# DCC_cDecoder.net
KiCad netlist of a schematic drawn in EAGLE
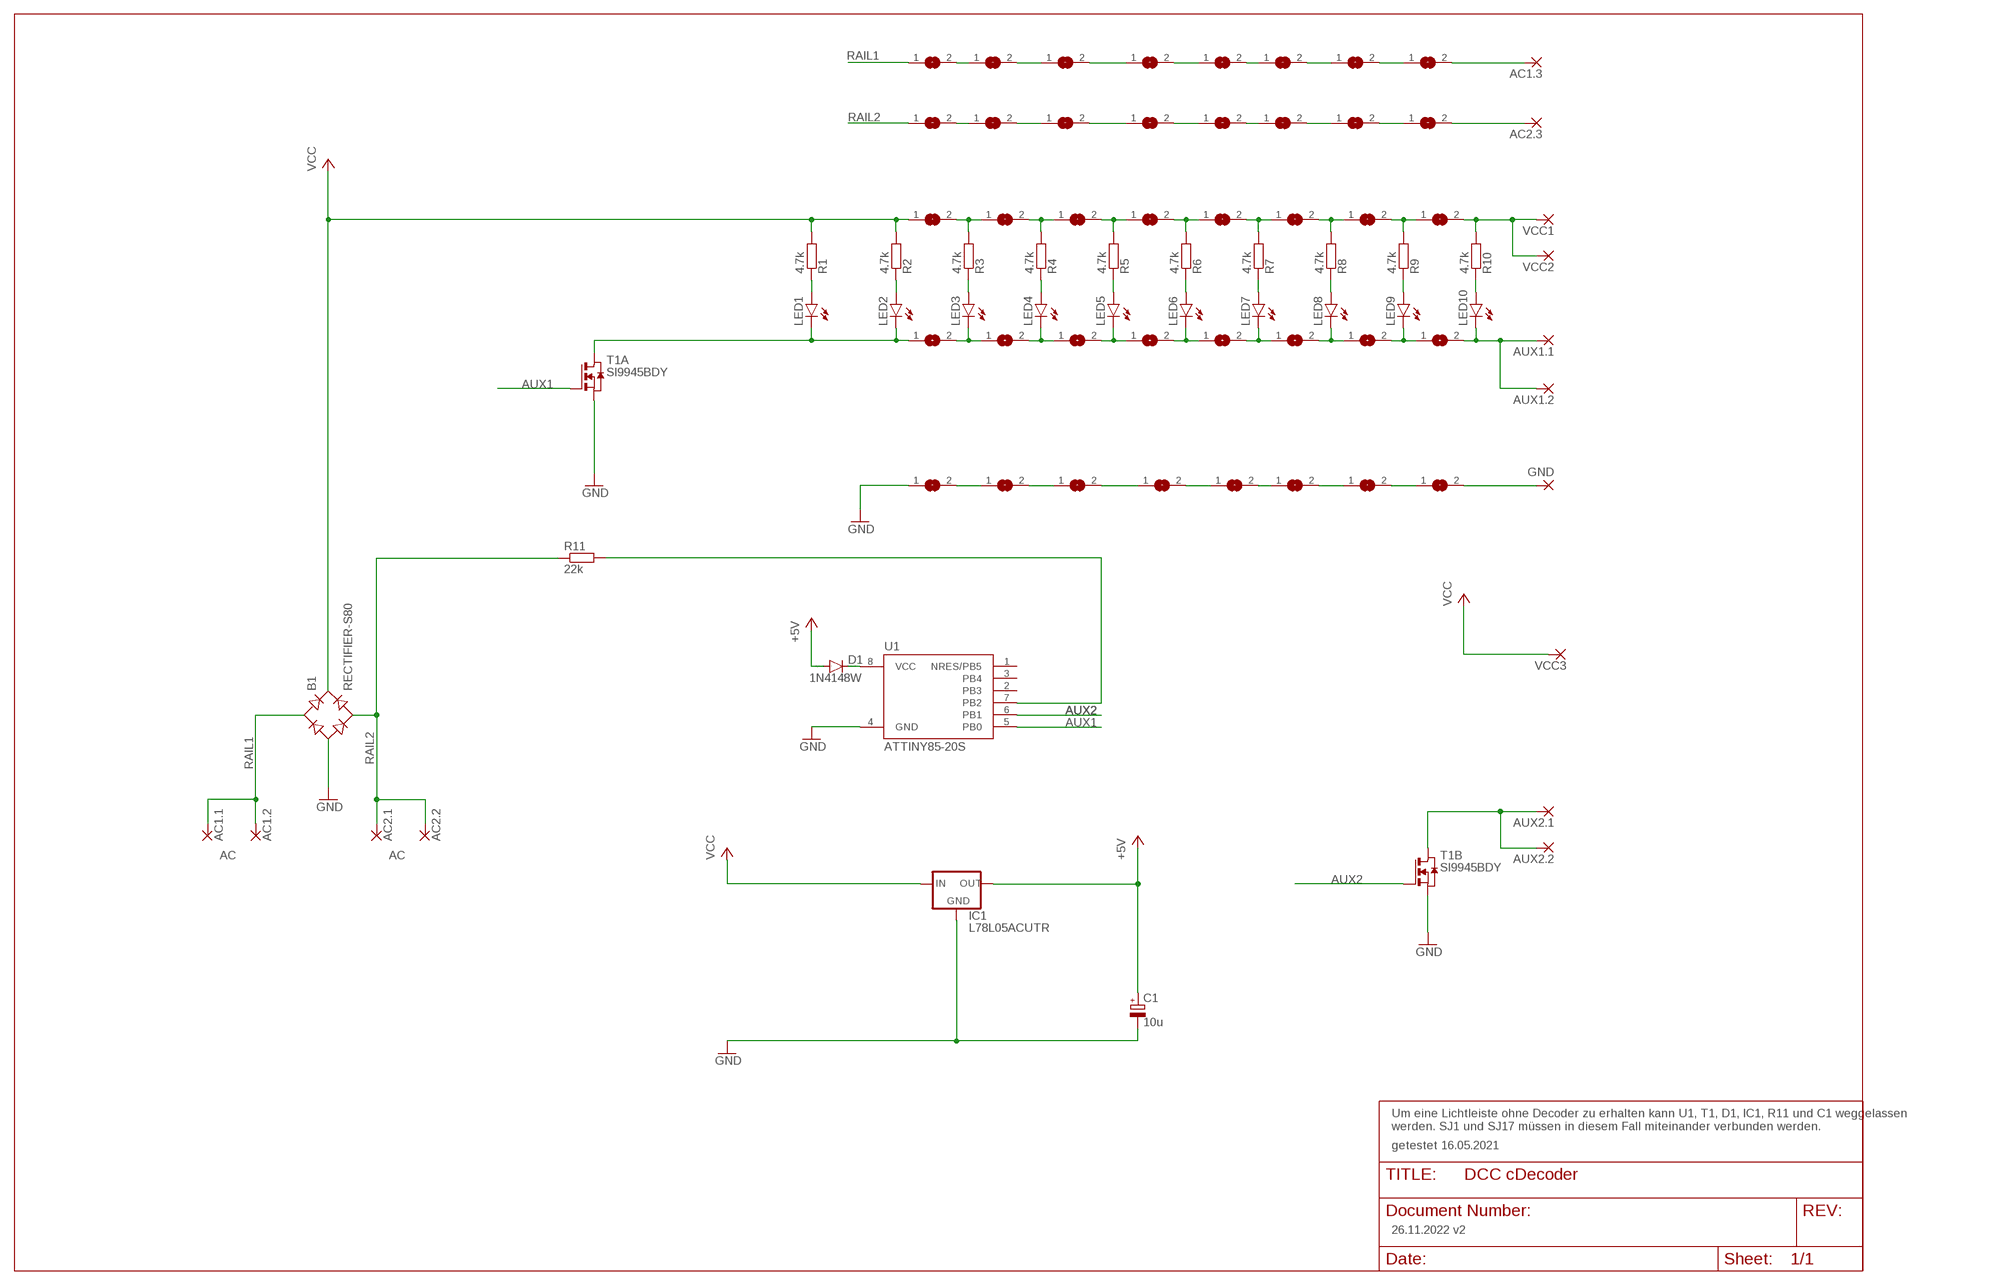
[diagram p0: schematic, sheet 1]

(export (version "E")
  (design (tool "Eeschema 10.0.6"))
  (components
    (comp (ref "AC1.1")
      (value "AC1.1")
      (footprint "eagle-import:SMD1,27-2,54")
      (libsource (lib "eagle-import") (part "SMD2"))
    )
    (comp (ref "AC1.2")
      (value "AC1.2")
      (footprint "eagle-import:SMD1,27-2,54")
      (libsource (lib "eagle-import") (part "SMD2"))
    )
    (comp (ref "AC1.3")
      (value "AC1.3")
      (footprint "eagle-import:SMD1,27-2,54")
      (libsource (lib "eagle-import") (part "SMD2"))
    )
    (comp (ref "AC2.1")
      (value "AC2.1")
      (footprint "eagle-import:SMD1,27-2,54")
      (libsource (lib "eagle-import") (part "SMD2"))
    )
    (comp (ref "AC2.2")
      (value "AC2.2")
      (footprint "eagle-import:SMD1,27-2,54")
      (libsource (lib "eagle-import") (part "SMD2"))
    )
    (comp (ref "AC2.3")
      (value "AC2.3")
      (footprint "eagle-import:SMD1,27-2,54")
      (libsource (lib "eagle-import") (part "SMD2"))
    )
    (comp (ref "AUX1.1")
      (value "AUX1.1")
      (footprint "eagle-import:SMD1,27-2,54")
      (libsource (lib "eagle-import") (part "SMD2"))
    )
    (comp (ref "AUX1.2")
      (value "AUX1.2")
      (footprint "eagle-import:SMD1,27-2,54")
      (libsource (lib "eagle-import") (part "SMD2"))
    )
    (comp (ref "AUX2.1")
      (value "AUX2.1")
      (footprint "eagle-import:SMD1,27-2,54")
      (libsource (lib "eagle-import") (part "SMD2"))
    )
    (comp (ref "AUX2.2")
      (value "AUX2.2")
      (footprint "eagle-import:SMD1,27-2,54")
      (libsource (lib "eagle-import") (part "SMD2"))
    )
    (comp (ref "B1")
      (value "RECTIFIER-S80")
      (footprint "eagle-import:TO-269AA")
      (libsource (lib "eagle-import") (part "RECTIFIER-S80"))
    )
    (comp (ref "C1")
      (value "10u")
      (footprint "eagle-import:A_3216-18W")
      (libsource (lib "eagle-import") (part "CPOL-EUA/3216-18W"))
    )
    (comp (ref "D1")
      (value "1N4148W")
      (footprint "eagle-import:SOD-123_MINI-SMA")
      (libsource (lib "eagle-import") (part "CGRM400-G1"))
    )
    (comp (ref "GND")
      (value "SMD2")
      (footprint "eagle-import:SMD1,27-2,54")
      (libsource (lib "eagle-import") (part "SMD2"))
    )
    (comp (ref "IC1")
      (value "L78L05ACUTR")
      (footprint "eagle-import:SOT89R")
      (libsource (lib "eagle-import") (part "L78L05ACUTR"))
    )
    (comp (ref "LED1")
      (value "LEDCHIPLED_0805")
      (footprint "eagle-import:CHIPLED_0805")
      (libsource (lib "eagle-import") (part "LEDCHIPLED_0805"))
    )
    (comp (ref "LED2")
      (value "LEDCHIPLED_0805")
      (footprint "eagle-import:CHIPLED_0805")
      (libsource (lib "eagle-import") (part "LEDCHIPLED_0805"))
    )
    (comp (ref "LED3")
      (value "LEDCHIPLED_0805")
      (footprint "eagle-import:CHIPLED_0805")
      (libsource (lib "eagle-import") (part "LEDCHIPLED_0805"))
    )
    (comp (ref "LED4")
      (value "LEDCHIPLED_0805")
      (footprint "eagle-import:CHIPLED_0805")
      (libsource (lib "eagle-import") (part "LEDCHIPLED_0805"))
    )
    (comp (ref "LED5")
      (value "LEDCHIPLED_0805")
      (footprint "eagle-import:CHIPLED_0805")
      (libsource (lib "eagle-import") (part "LEDCHIPLED_0805"))
    )
    (comp (ref "LED6")
      (value "LEDCHIPLED_0805")
      (footprint "eagle-import:CHIPLED_0805")
      (libsource (lib "eagle-import") (part "LEDCHIPLED_0805"))
    )
    (comp (ref "LED7")
      (value "LEDCHIPLED_0805")
      (footprint "eagle-import:CHIPLED_0805")
      (libsource (lib "eagle-import") (part "LEDCHIPLED_0805"))
    )
    (comp (ref "LED8")
      (value "LEDCHIPLED_0805")
      (footprint "eagle-import:CHIPLED_0805")
      (libsource (lib "eagle-import") (part "LEDCHIPLED_0805"))
    )
    (comp (ref "LED9")
      (value "LEDCHIPLED_0805")
      (footprint "eagle-import:CHIPLED_0805")
      (libsource (lib "eagle-import") (part "LEDCHIPLED_0805"))
    )
    (comp (ref "LED10")
      (value "LEDCHIPLED_0805")
      (footprint "eagle-import:CHIPLED_0805")
      (libsource (lib "eagle-import") (part "LEDCHIPLED_0805"))
    )
    (comp (ref "R1")
      (value "4.7k")
      (footprint "eagle-import:R0805")
      (libsource (lib "eagle-import") (part "R-EU_R0805"))
    )
    (comp (ref "R2")
      (value "4.7k")
      (footprint "eagle-import:R0805")
      (libsource (lib "eagle-import") (part "R-EU_R0805"))
    )
    (comp (ref "R3")
      (value "4.7k")
      (footprint "eagle-import:R0805")
      (libsource (lib "eagle-import") (part "R-EU_R0805"))
    )
    (comp (ref "R4")
      (value "4.7k")
      (footprint "eagle-import:R0805")
      (libsource (lib "eagle-import") (part "R-EU_R0805"))
    )
    (comp (ref "R5")
      (value "4.7k")
      (footprint "eagle-import:R0805")
      (libsource (lib "eagle-import") (part "R-EU_R0805"))
    )
    (comp (ref "R6")
      (value "4.7k")
      (footprint "eagle-import:R0805")
      (libsource (lib "eagle-import") (part "R-EU_R0805"))
    )
    (comp (ref "R7")
      (value "4.7k")
      (footprint "eagle-import:R0805")
      (libsource (lib "eagle-import") (part "R-EU_R0805"))
    )
    (comp (ref "R8")
      (value "4.7k")
      (footprint "eagle-import:R0805")
      (libsource (lib "eagle-import") (part "R-EU_R0805"))
    )
    (comp (ref "R9")
      (value "4.7k")
      (footprint "eagle-import:R0805")
      (libsource (lib "eagle-import") (part "R-EU_R0805"))
    )
    (comp (ref "R10")
      (value "4.7k")
      (footprint "eagle-import:R0805")
      (libsource (lib "eagle-import") (part "R-EU_R0805"))
    )
    (comp (ref "R11")
      (value "22k")
      (footprint "eagle-import:R0805")
      (libsource (lib "eagle-import") (part "R-EU_R0805"))
    )
    (comp (ref "SJ1")
      (value "SJC")
      (footprint "eagle-import:SJC")
      (libsource (lib "eagle-import") (part "SJC"))
    )
    (comp (ref "SJ2")
      (value "SJC")
      (footprint "eagle-import:SJC")
      (libsource (lib "eagle-import") (part "SJC"))
    )
    (comp (ref "SJ3")
      (value "SJC")
      (footprint "eagle-import:SJC")
      (libsource (lib "eagle-import") (part "SJC"))
    )
    (comp (ref "SJ4")
      (value "SJC")
      (footprint "eagle-import:SJC")
      (libsource (lib "eagle-import") (part "SJC"))
    )
    (comp (ref "SJ5")
      (value "SJC")
      (footprint "eagle-import:SJC")
      (libsource (lib "eagle-import") (part "SJC"))
    )
    (comp (ref "SJ6")
      (value "SJC")
      (footprint "eagle-import:SJC")
      (libsource (lib "eagle-import") (part "SJC"))
    )
    (comp (ref "SJ7")
      (value "SJC")
      (footprint "eagle-import:SJC")
      (libsource (lib "eagle-import") (part "SJC"))
    )
    (comp (ref "SJ8")
      (value "SJC")
      (footprint "eagle-import:SJC")
      (libsource (lib "eagle-import") (part "SJC"))
    )
    (comp (ref "SJ9")
      (value "SJC")
      (footprint "eagle-import:SJC")
      (libsource (lib "eagle-import") (part "SJC"))
    )
    (comp (ref "SJ10")
      (value "SJC")
      (footprint "eagle-import:SJC")
      (libsource (lib "eagle-import") (part "SJC"))
    )
    (comp (ref "SJ11")
      (value "SJC")
      (footprint "eagle-import:SJC")
      (libsource (lib "eagle-import") (part "SJC"))
    )
    (comp (ref "SJ12")
      (value "SJC")
      (footprint "eagle-import:SJC")
      (libsource (lib "eagle-import") (part "SJC"))
    )
    (comp (ref "SJ13")
      (value "SJC")
      (footprint "eagle-import:SJC")
      (libsource (lib "eagle-import") (part "SJC"))
    )
    (comp (ref "SJ14")
      (value "SJC")
      (footprint "eagle-import:SJC")
      (libsource (lib "eagle-import") (part "SJC"))
    )
    (comp (ref "SJ15")
      (value "SJC")
      (footprint "eagle-import:SJC")
      (libsource (lib "eagle-import") (part "SJC"))
    )
    (comp (ref "SJ16")
      (value "SJC")
      (footprint "eagle-import:SJC")
      (libsource (lib "eagle-import") (part "SJC"))
    )
    (comp (ref "SJ17")
      (value "SJ")
      (footprint "eagle-import:SJ")
      (libsource (lib "eagle-import") (part "SJ"))
    )
    (comp (ref "SJ18")
      (value "SJ")
      (footprint "eagle-import:SJ")
      (libsource (lib "eagle-import") (part "SJ"))
    )
    (comp (ref "SJ19")
      (value "SJ")
      (footprint "eagle-import:SJ")
      (libsource (lib "eagle-import") (part "SJ"))
    )
    (comp (ref "SJ20")
      (value "SJ")
      (footprint "eagle-import:SJ")
      (libsource (lib "eagle-import") (part "SJ"))
    )
    (comp (ref "SJ21")
      (value "SJ")
      (footprint "eagle-import:SJ")
      (libsource (lib "eagle-import") (part "SJ"))
    )
    (comp (ref "SJ22")
      (value "SJ")
      (footprint "eagle-import:SJ")
      (libsource (lib "eagle-import") (part "SJ"))
    )
    (comp (ref "SJ23")
      (value "SJ")
      (footprint "eagle-import:SJ")
      (libsource (lib "eagle-import") (part "SJ"))
    )
    (comp (ref "SJ24")
      (value "SJ")
      (footprint "eagle-import:SJ")
      (libsource (lib "eagle-import") (part "SJ"))
    )
    (comp (ref "SJ25")
      (value "SJC")
      (footprint "eagle-import:SJC")
      (libsource (lib "eagle-import") (part "SJC"))
    )
    (comp (ref "SJ26")
      (value "SJC")
      (footprint "eagle-import:SJC")
      (libsource (lib "eagle-import") (part "SJC"))
    )
    (comp (ref "SJ27")
      (value "SJC")
      (footprint "eagle-import:SJC")
      (libsource (lib "eagle-import") (part "SJC"))
    )
    (comp (ref "SJ28")
      (value "SJC")
      (footprint "eagle-import:SJC")
      (libsource (lib "eagle-import") (part "SJC"))
    )
    (comp (ref "SJ29")
      (value "SJC")
      (footprint "eagle-import:SJC")
      (libsource (lib "eagle-import") (part "SJC"))
    )
    (comp (ref "SJ30")
      (value "SJC")
      (footprint "eagle-import:SJC")
      (libsource (lib "eagle-import") (part "SJC"))
    )
    (comp (ref "SJ31")
      (value "SJC")
      (footprint "eagle-import:SJC")
      (libsource (lib "eagle-import") (part "SJC"))
    )
    (comp (ref "SJ32")
      (value "SJC")
      (footprint "eagle-import:SJC")
      (libsource (lib "eagle-import") (part "SJC"))
    )
    (comp (ref "SJ33")
      (value "SJC")
      (footprint "eagle-import:SJC")
      (libsource (lib "eagle-import") (part "SJC"))
    )
    (comp (ref "SJ34")
      (value "SJC")
      (footprint "eagle-import:SJC")
      (libsource (lib "eagle-import") (part "SJC"))
    )
    (comp (ref "SJ35")
      (value "SJC")
      (footprint "eagle-import:SJC")
      (libsource (lib "eagle-import") (part "SJC"))
    )
    (comp (ref "SJ36")
      (value "SJC")
      (footprint "eagle-import:SJC")
      (libsource (lib "eagle-import") (part "SJC"))
    )
    (comp (ref "SJ37")
      (value "SJC")
      (footprint "eagle-import:SJC")
      (libsource (lib "eagle-import") (part "SJC"))
    )
    (comp (ref "SJ38")
      (value "SJC")
      (footprint "eagle-import:SJC")
      (libsource (lib "eagle-import") (part "SJC"))
    )
    (comp (ref "SJ39")
      (value "SJC")
      (footprint "eagle-import:SJC")
      (libsource (lib "eagle-import") (part "SJC"))
    )
    (comp (ref "SJ40")
      (value "SJC")
      (footprint "eagle-import:SJC")
      (libsource (lib "eagle-import") (part "SJC"))
    )
    (comp (ref "T1")
      (value "SI9945BDY")
      (footprint "eagle-import:SO8")
      (libsource (lib "eagle-import") (part "NMOS2SO8"))
    )
    (comp (ref "U1")
      (value "ATTINY85-20S")
      (footprint "eagle-import:SOIC8_EIAJ_208MIL")
      (libsource (lib "eagle-import") (part "ATTINY85S-20"))
    )
    (comp (ref "VCC1")
      (value "VCC1")
      (footprint "eagle-import:SMD1,27-2,54")
      (libsource (lib "eagle-import") (part "SMD2"))
    )
    (comp (ref "VCC2")
      (value "VCC2")
      (footprint "eagle-import:SMD1,27-2,54")
      (libsource (lib "eagle-import") (part "SMD2"))
    )
    (comp (ref "VCC3")
      (value "VCC3")
      (footprint "eagle-import:SMD1,27-2,54")
      (libsource (lib "eagle-import") (part "SMD2"))
    )
  )
  (nets
    (net (code "1") (name "+5V") (class "Default")
      (node (ref "C1") (pin "+") (pinfunction "+_+") (pintype "passive"))
      (node (ref "D1") (pin "A") (pinfunction "A_A") (pintype "passive"))
      (node (ref "IC1") (pin "2") (pinfunction "OUT_2") (pintype "passive"))
    )
    (net (code "2") (name "/AUX1") (class "Default")
      (node (ref "T1") (pin "2") (pinfunction "G_2") (pintype "passive"))
      (node (ref "U1") (pin "5") (pinfunction "PB0_5") (pintype "bidirectional"))
    )
    (net (code "3") (name "/AUX2") (class "Default")
      (node (ref "T1") (pin "4") (pinfunction "G_4") (pintype "passive"))
      (node (ref "U1") (pin "6") (pinfunction "PB1_6") (pintype "bidirectional"))
    )
    (net (code "4") (name "/RAIL1") (class "Default")
      (node (ref "AC1.1") (pin "1") (pinfunction "P_1") (pintype "passive"))
      (node (ref "AC1.2") (pin "1") (pinfunction "P_1") (pintype "passive"))
      (node (ref "B1") (pin "AC1") (pinfunction "AC1_AC1") (pintype "passive"))
      (node (ref "SJ25") (pin "1") (pinfunction "1_1") (pintype "passive"))
    )
    (net (code "5") (name "/RAIL2") (class "Default")
      (node (ref "AC2.1") (pin "1") (pinfunction "P_1") (pintype "passive"))
      (node (ref "AC2.2") (pin "1") (pinfunction "P_1") (pintype "passive"))
      (node (ref "B1") (pin "AC2") (pinfunction "AC2_AC2") (pintype "passive"))
      (node (ref "R11") (pin "1") (pinfunction "1_1") (pintype "passive"))
      (node (ref "SJ33") (pin "1") (pinfunction "1_1") (pintype "passive"))
    )
    (net (code "6") (name "GND") (class "Default")
      (node (ref "B1") (pin "-") (pinfunction "-_-") (pintype "passive"))
      (node (ref "C1") (pin "-") (pinfunction "-_-") (pintype "passive"))
      (node (ref "IC1") (pin "3") (pinfunction "GND_3") (pintype "input"))
      (node (ref "IC1") (pin "4") (pinfunction "GND_4") (pintype "input"))
      (node (ref "SJ1") (pin "1") (pinfunction "1_1") (pintype "passive"))
      (node (ref "T1") (pin "1") (pinfunction "S_1") (pintype "passive"))
      (node (ref "T1") (pin "3") (pinfunction "S_3") (pintype "passive"))
      (node (ref "U1") (pin "4") (pinfunction "GND_4") (pintype "power_in"))
    )
    (net (code "7") (name "Net-(AC1.3-P)") (class "Default")
      (node (ref "AC1.3") (pin "1") (pinfunction "P_1") (pintype "passive"))
      (node (ref "SJ32") (pin "2") (pinfunction "2_2") (pintype "passive"))
    )
    (net (code "8") (name "Net-(AC2.3-P)") (class "Default")
      (node (ref "AC2.3") (pin "1") (pinfunction "P_1") (pintype "passive"))
      (node (ref "SJ40") (pin "2") (pinfunction "2_2") (pintype "passive"))
    )
    (net (code "9") (name "Net-(AUX1.1-P)") (class "Default")
      (node (ref "AUX1.1") (pin "1") (pinfunction "P_1") (pintype "passive"))
      (node (ref "AUX1.2") (pin "1") (pinfunction "P_1") (pintype "passive"))
      (node (ref "LED10") (pin "C") (pinfunction "C_C") (pintype "passive"))
      (node (ref "SJ24") (pin "2") (pinfunction "2_2") (pintype "passive"))
    )
    (net (code "10") (name "Net-(AUX2.1-P)") (class "Default")
      (node (ref "AUX2.1") (pin "1") (pinfunction "P_1") (pintype "passive"))
      (node (ref "AUX2.2") (pin "1") (pinfunction "P_1") (pintype "passive"))
      (node (ref "T1") (pin "5") (pinfunction "D_5") (pintype "passive"))
      (node (ref "T1") (pin "6") (pinfunction "D_6") (pintype "passive"))
    )
    (net (code "11") (name "Net-(GND-P)") (class "Default")
      (node (ref "GND") (pin "1") (pinfunction "P_1") (pintype "passive"))
      (node (ref "SJ15") (pin "2") (pinfunction "2_2") (pintype "passive"))
    )
    (net (code "12") (name "Net-(LED1-PadA)") (class "Default")
      (node (ref "LED1") (pin "A") (pinfunction "A_A") (pintype "passive"))
      (node (ref "R1") (pin "1") (pinfunction "1_1") (pintype "passive"))
    )
    (net (code "13") (name "Net-(LED1-PadC)") (class "Default")
      (node (ref "LED1") (pin "C") (pinfunction "C_C") (pintype "passive"))
      (node (ref "LED2") (pin "C") (pinfunction "C_C") (pintype "passive"))
      (node (ref "SJ17") (pin "1") (pinfunction "1_1") (pintype "passive"))
      (node (ref "T1") (pin "7") (pinfunction "D_7") (pintype "passive"))
      (node (ref "T1") (pin "8") (pinfunction "D_8") (pintype "passive"))
    )
    (net (code "14") (name "Net-(LED2-PadA)") (class "Default")
      (node (ref "LED2") (pin "A") (pinfunction "A_A") (pintype "passive"))
      (node (ref "R2") (pin "1") (pinfunction "1_1") (pintype "passive"))
    )
    (net (code "15") (name "Net-(LED3-PadA)") (class "Default")
      (node (ref "LED3") (pin "A") (pinfunction "A_A") (pintype "passive"))
      (node (ref "R3") (pin "1") (pinfunction "1_1") (pintype "passive"))
    )
    (net (code "16") (name "Net-(LED3-PadC)") (class "Default")
      (node (ref "LED3") (pin "C") (pinfunction "C_C") (pintype "passive"))
      (node (ref "SJ17") (pin "2") (pinfunction "2_2") (pintype "passive"))
      (node (ref "SJ18") (pin "1") (pinfunction "1_1") (pintype "passive"))
    )
    (net (code "17") (name "Net-(LED4-PadA)") (class "Default")
      (node (ref "LED4") (pin "A") (pinfunction "A_A") (pintype "passive"))
      (node (ref "R4") (pin "1") (pinfunction "1_1") (pintype "passive"))
    )
    (net (code "18") (name "Net-(LED4-PadC)") (class "Default")
      (node (ref "LED4") (pin "C") (pinfunction "C_C") (pintype "passive"))
      (node (ref "SJ18") (pin "2") (pinfunction "2_2") (pintype "passive"))
      (node (ref "SJ19") (pin "1") (pinfunction "1_1") (pintype "passive"))
    )
    (net (code "19") (name "Net-(LED5-PadA)") (class "Default")
      (node (ref "LED5") (pin "A") (pinfunction "A_A") (pintype "passive"))
      (node (ref "R5") (pin "1") (pinfunction "1_1") (pintype "passive"))
    )
    (net (code "20") (name "Net-(LED5-PadC)") (class "Default")
      (node (ref "LED5") (pin "C") (pinfunction "C_C") (pintype "passive"))
      (node (ref "SJ19") (pin "2") (pinfunction "2_2") (pintype "passive"))
      (node (ref "SJ20") (pin "1") (pinfunction "1_1") (pintype "passive"))
    )
    (net (code "21") (name "Net-(LED6-PadA)") (class "Default")
      (node (ref "LED6") (pin "A") (pinfunction "A_A") (pintype "passive"))
      (node (ref "R6") (pin "1") (pinfunction "1_1") (pintype "passive"))
    )
    (net (code "22") (name "Net-(LED6-PadC)") (class "Default")
      (node (ref "LED6") (pin "C") (pinfunction "C_C") (pintype "passive"))
      (node (ref "SJ20") (pin "2") (pinfunction "2_2") (pintype "passive"))
      (node (ref "SJ21") (pin "1") (pinfunction "1_1") (pintype "passive"))
    )
    (net (code "23") (name "Net-(LED7-PadA)") (class "Default")
      (node (ref "LED7") (pin "A") (pinfunction "A_A") (pintype "passive"))
      (node (ref "R7") (pin "1") (pinfunction "1_1") (pintype "passive"))
    )
    (net (code "24") (name "Net-(LED7-PadC)") (class "Default")
      (node (ref "LED7") (pin "C") (pinfunction "C_C") (pintype "passive"))
      (node (ref "SJ21") (pin "2") (pinfunction "2_2") (pintype "passive"))
      (node (ref "SJ22") (pin "1") (pinfunction "1_1") (pintype "passive"))
    )
    (net (code "25") (name "Net-(LED8-PadA)") (class "Default")
      (node (ref "LED8") (pin "A") (pinfunction "A_A") (pintype "passive"))
      (node (ref "R8") (pin "1") (pinfunction "1_1") (pintype "passive"))
    )
    (net (code "26") (name "Net-(LED8-PadC)") (class "Default")
      (node (ref "LED8") (pin "C") (pinfunction "C_C") (pintype "passive"))
      (node (ref "SJ22") (pin "2") (pinfunction "2_2") (pintype "passive"))
      (node (ref "SJ23") (pin "1") (pinfunction "1_1") (pintype "passive"))
    )
    (net (code "27") (name "Net-(LED9-PadA)") (class "Default")
      (node (ref "LED9") (pin "A") (pinfunction "A_A") (pintype "passive"))
      (node (ref "R9") (pin "1") (pinfunction "1_1") (pintype "passive"))
    )
    (net (code "28") (name "Net-(LED9-PadC)") (class "Default")
      (node (ref "LED9") (pin "C") (pinfunction "C_C") (pintype "passive"))
      (node (ref "SJ23") (pin "2") (pinfunction "2_2") (pintype "passive"))
      (node (ref "SJ24") (pin "1") (pinfunction "1_1") (pintype "passive"))
    )
    (net (code "29") (name "Net-(LED10-PadA)") (class "Default")
      (node (ref "LED10") (pin "A") (pinfunction "A_A") (pintype "passive"))
      (node (ref "R10") (pin "1") (pinfunction "1_1") (pintype "passive"))
    )
    (net (code "30") (name "Net-(R3-Pad2)") (class "Default")
      (node (ref "R3") (pin "2") (pinfunction "2_2") (pintype "passive"))
      (node (ref "SJ2") (pin "2") (pinfunction "2_2") (pintype "passive"))
      (node (ref "SJ4") (pin "1") (pinfunction "1_1") (pintype "passive"))
    )
    (net (code "31") (name "Net-(R4-Pad2)") (class "Default")
      (node (ref "R4") (pin "2") (pinfunction "2_2") (pintype "passive"))
      (node (ref "SJ4") (pin "2") (pinfunction "2_2") (pintype "passive"))
      (node (ref "SJ6") (pin "1") (pinfunction "1_1") (pintype "passive"))
    )
    (net (code "32") (name "Net-(R5-Pad2)") (class "Default")
      (node (ref "R5") (pin "2") (pinfunction "2_2") (pintype "passive"))
      (node (ref "SJ6") (pin "2") (pinfunction "2_2") (pintype "passive"))
      (node (ref "SJ8") (pin "1") (pinfunction "1_1") (pintype "passive"))
    )
    (net (code "33") (name "Net-(R6-Pad2)") (class "Default")
      (node (ref "R6") (pin "2") (pinfunction "2_2") (pintype "passive"))
      (node (ref "SJ10") (pin "1") (pinfunction "1_1") (pintype "passive"))
      (node (ref "SJ8") (pin "2") (pinfunction "2_2") (pintype "passive"))
    )
    (net (code "34") (name "Net-(R7-Pad2)") (class "Default")
      (node (ref "R7") (pin "2") (pinfunction "2_2") (pintype "passive"))
      (node (ref "SJ10") (pin "2") (pinfunction "2_2") (pintype "passive"))
      (node (ref "SJ12") (pin "1") (pinfunction "1_1") (pintype "passive"))
    )
    (net (code "35") (name "Net-(R8-Pad2)") (class "Default")
      (node (ref "R8") (pin "2") (pinfunction "2_2") (pintype "passive"))
      (node (ref "SJ12") (pin "2") (pinfunction "2_2") (pintype "passive"))
      (node (ref "SJ14") (pin "1") (pinfunction "1_1") (pintype "passive"))
    )
    (net (code "36") (name "Net-(R9-Pad2)") (class "Default")
      (node (ref "R9") (pin "2") (pinfunction "2_2") (pintype "passive"))
      (node (ref "SJ14") (pin "2") (pinfunction "2_2") (pintype "passive"))
      (node (ref "SJ16") (pin "1") (pinfunction "1_1") (pintype "passive"))
    )
    (net (code "37") (name "Net-(SJ1-Pad2)") (class "Default")
      (node (ref "SJ1") (pin "2") (pinfunction "2_2") (pintype "passive"))
      (node (ref "SJ3") (pin "1") (pinfunction "1_1") (pintype "passive"))
    )
    (net (code "38") (name "Net-(SJ3-Pad2)") (class "Default")
      (node (ref "SJ3") (pin "2") (pinfunction "2_2") (pintype "passive"))
      (node (ref "SJ5") (pin "1") (pinfunction "1_1") (pintype "passive"))
    )
    (net (code "39") (name "Net-(SJ5-Pad2)") (class "Default")
      (node (ref "SJ5") (pin "2") (pinfunction "2_2") (pintype "passive"))
      (node (ref "SJ7") (pin "1") (pinfunction "1_1") (pintype "passive"))
    )
    (net (code "40") (name "Net-(SJ7-Pad2)") (class "Default")
      (node (ref "SJ7") (pin "2") (pinfunction "2_2") (pintype "passive"))
      (node (ref "SJ9") (pin "1") (pinfunction "1_1") (pintype "passive"))
    )
    (net (code "41") (name "Net-(SJ11-Pad1)") (class "Default")
      (node (ref "SJ11") (pin "1") (pinfunction "1_1") (pintype "passive"))
      (node (ref "SJ9") (pin "2") (pinfunction "2_2") (pintype "passive"))
    )
    (net (code "42") (name "Net-(SJ11-Pad2)") (class "Default")
      (node (ref "SJ11") (pin "2") (pinfunction "2_2") (pintype "passive"))
      (node (ref "SJ13") (pin "1") (pinfunction "1_1") (pintype "passive"))
    )
    (net (code "43") (name "Net-(SJ13-Pad2)") (class "Default")
      (node (ref "SJ13") (pin "2") (pinfunction "2_2") (pintype "passive"))
      (node (ref "SJ15") (pin "1") (pinfunction "1_1") (pintype "passive"))
    )
    (net (code "44") (name "Net-(SJ25-Pad2)") (class "Default")
      (node (ref "SJ25") (pin "2") (pinfunction "2_2") (pintype "passive"))
      (node (ref "SJ26") (pin "1") (pinfunction "1_1") (pintype "passive"))
    )
    (net (code "45") (name "Net-(SJ26-Pad2)") (class "Default")
      (node (ref "SJ26") (pin "2") (pinfunction "2_2") (pintype "passive"))
      (node (ref "SJ27") (pin "1") (pinfunction "1_1") (pintype "passive"))
    )
    (net (code "46") (name "Net-(SJ27-Pad2)") (class "Default")
      (node (ref "SJ27") (pin "2") (pinfunction "2_2") (pintype "passive"))
      (node (ref "SJ28") (pin "1") (pinfunction "1_1") (pintype "passive"))
    )
    (net (code "47") (name "Net-(SJ28-Pad2)") (class "Default")
      (node (ref "SJ28") (pin "2") (pinfunction "2_2") (pintype "passive"))
      (node (ref "SJ29") (pin "1") (pinfunction "1_1") (pintype "passive"))
    )
    (net (code "48") (name "Net-(SJ29-Pad2)") (class "Default")
      (node (ref "SJ29") (pin "2") (pinfunction "2_2") (pintype "passive"))
      (node (ref "SJ30") (pin "1") (pinfunction "1_1") (pintype "passive"))
    )
    (net (code "49") (name "Net-(SJ30-Pad2)") (class "Default")
      (node (ref "SJ30") (pin "2") (pinfunction "2_2") (pintype "passive"))
      (node (ref "SJ31") (pin "1") (pinfunction "1_1") (pintype "passive"))
    )
    (net (code "50") (name "Net-(SJ31-Pad2)") (class "Default")
      (node (ref "SJ31") (pin "2") (pinfunction "2_2") (pintype "passive"))
      (node (ref "SJ32") (pin "1") (pinfunction "1_1") (pintype "passive"))
    )
    (net (code "51") (name "Net-(SJ33-Pad2)") (class "Default")
      (node (ref "SJ33") (pin "2") (pinfunction "2_2") (pintype "passive"))
      (node (ref "SJ34") (pin "1") (pinfunction "1_1") (pintype "passive"))
    )
    (net (code "52") (name "Net-(SJ34-Pad2)") (class "Default")
      (node (ref "SJ34") (pin "2") (pinfunction "2_2") (pintype "passive"))
      (node (ref "SJ35") (pin "1") (pinfunction "1_1") (pintype "passive"))
    )
    (net (code "53") (name "Net-(SJ35-Pad2)") (class "Default")
      (node (ref "SJ35") (pin "2") (pinfunction "2_2") (pintype "passive"))
      (node (ref "SJ36") (pin "1") (pinfunction "1_1") (pintype "passive"))
    )
    (net (code "54") (name "Net-(SJ36-Pad2)") (class "Default")
      (node (ref "SJ36") (pin "2") (pinfunction "2_2") (pintype "passive"))
      (node (ref "SJ37") (pin "1") (pinfunction "1_1") (pintype "passive"))
    )
    (net (code "55") (name "Net-(SJ37-Pad2)") (class "Default")
      (node (ref "SJ37") (pin "2") (pinfunction "2_2") (pintype "passive"))
      (node (ref "SJ38") (pin "1") (pinfunction "1_1") (pintype "passive"))
    )
    (net (code "56") (name "Net-(SJ38-Pad2)") (class "Default")
      (node (ref "SJ38") (pin "2") (pinfunction "2_2") (pintype "passive"))
      (node (ref "SJ39") (pin "1") (pinfunction "1_1") (pintype "passive"))
    )
    (net (code "57") (name "Net-(SJ39-Pad2)") (class "Default")
      (node (ref "SJ39") (pin "2") (pinfunction "2_2") (pintype "passive"))
      (node (ref "SJ40") (pin "1") (pinfunction "1_1") (pintype "passive"))
    )
    (net (code "58") (name "Net-(U1-PB2)") (class "Default")
      (node (ref "R11") (pin "2") (pinfunction "2_2") (pintype "passive"))
      (node (ref "U1") (pin "7") (pinfunction "PB2_7") (pintype "bidirectional"))
    )
    (net (code "59") (name "Net-(U1-VCC)") (class "Default")
      (node (ref "D1") (pin "C") (pinfunction "C_C") (pintype "passive"))
      (node (ref "U1") (pin "8") (pinfunction "VCC_8") (pintype "power_in"))
    )
    (net (code "60") (name "Net-(VCC1-P)") (class "Default")
      (node (ref "R10") (pin "2") (pinfunction "2_2") (pintype "passive"))
      (node (ref "SJ16") (pin "2") (pinfunction "2_2") (pintype "passive"))
      (node (ref "VCC1") (pin "1") (pinfunction "P_1") (pintype "passive"))
      (node (ref "VCC2") (pin "1") (pinfunction "P_1") (pintype "passive"))
    )
    (net (code "61") (name "VCC") (class "Default")
      (node (ref "B1") (pin "+") (pinfunction "+_+") (pintype "passive"))
      (node (ref "IC1") (pin "1") (pinfunction "IN_1") (pintype "input"))
      (node (ref "R1") (pin "2") (pinfunction "2_2") (pintype "passive"))
      (node (ref "R2") (pin "2") (pinfunction "2_2") (pintype "passive"))
      (node (ref "SJ2") (pin "1") (pinfunction "1_1") (pintype "passive"))
      (node (ref "VCC3") (pin "1") (pinfunction "P_1") (pintype "passive"))
    )
    (net (code "62") (name "unconnected-(U1-NRES{slash}PB5-Pad1)") (class "Default")
      (node (ref "U1") (pin "1") (pinfunction "NRES/PB5_1") (pintype "bidirectional"))
    )
    (net (code "63") (name "unconnected-(U1-PB3-Pad2)") (class "Default")
      (node (ref "U1") (pin "2") (pinfunction "PB3_2") (pintype "bidirectional"))
    )
    (net (code "64") (name "unconnected-(U1-PB4-Pad3)") (class "Default")
      (node (ref "U1") (pin "3") (pinfunction "PB4_3") (pintype "bidirectional"))
    )
  )
)
